# STM32WL_LHCbit.net
KiCad netlist of a schematic drawn in Altium Designer
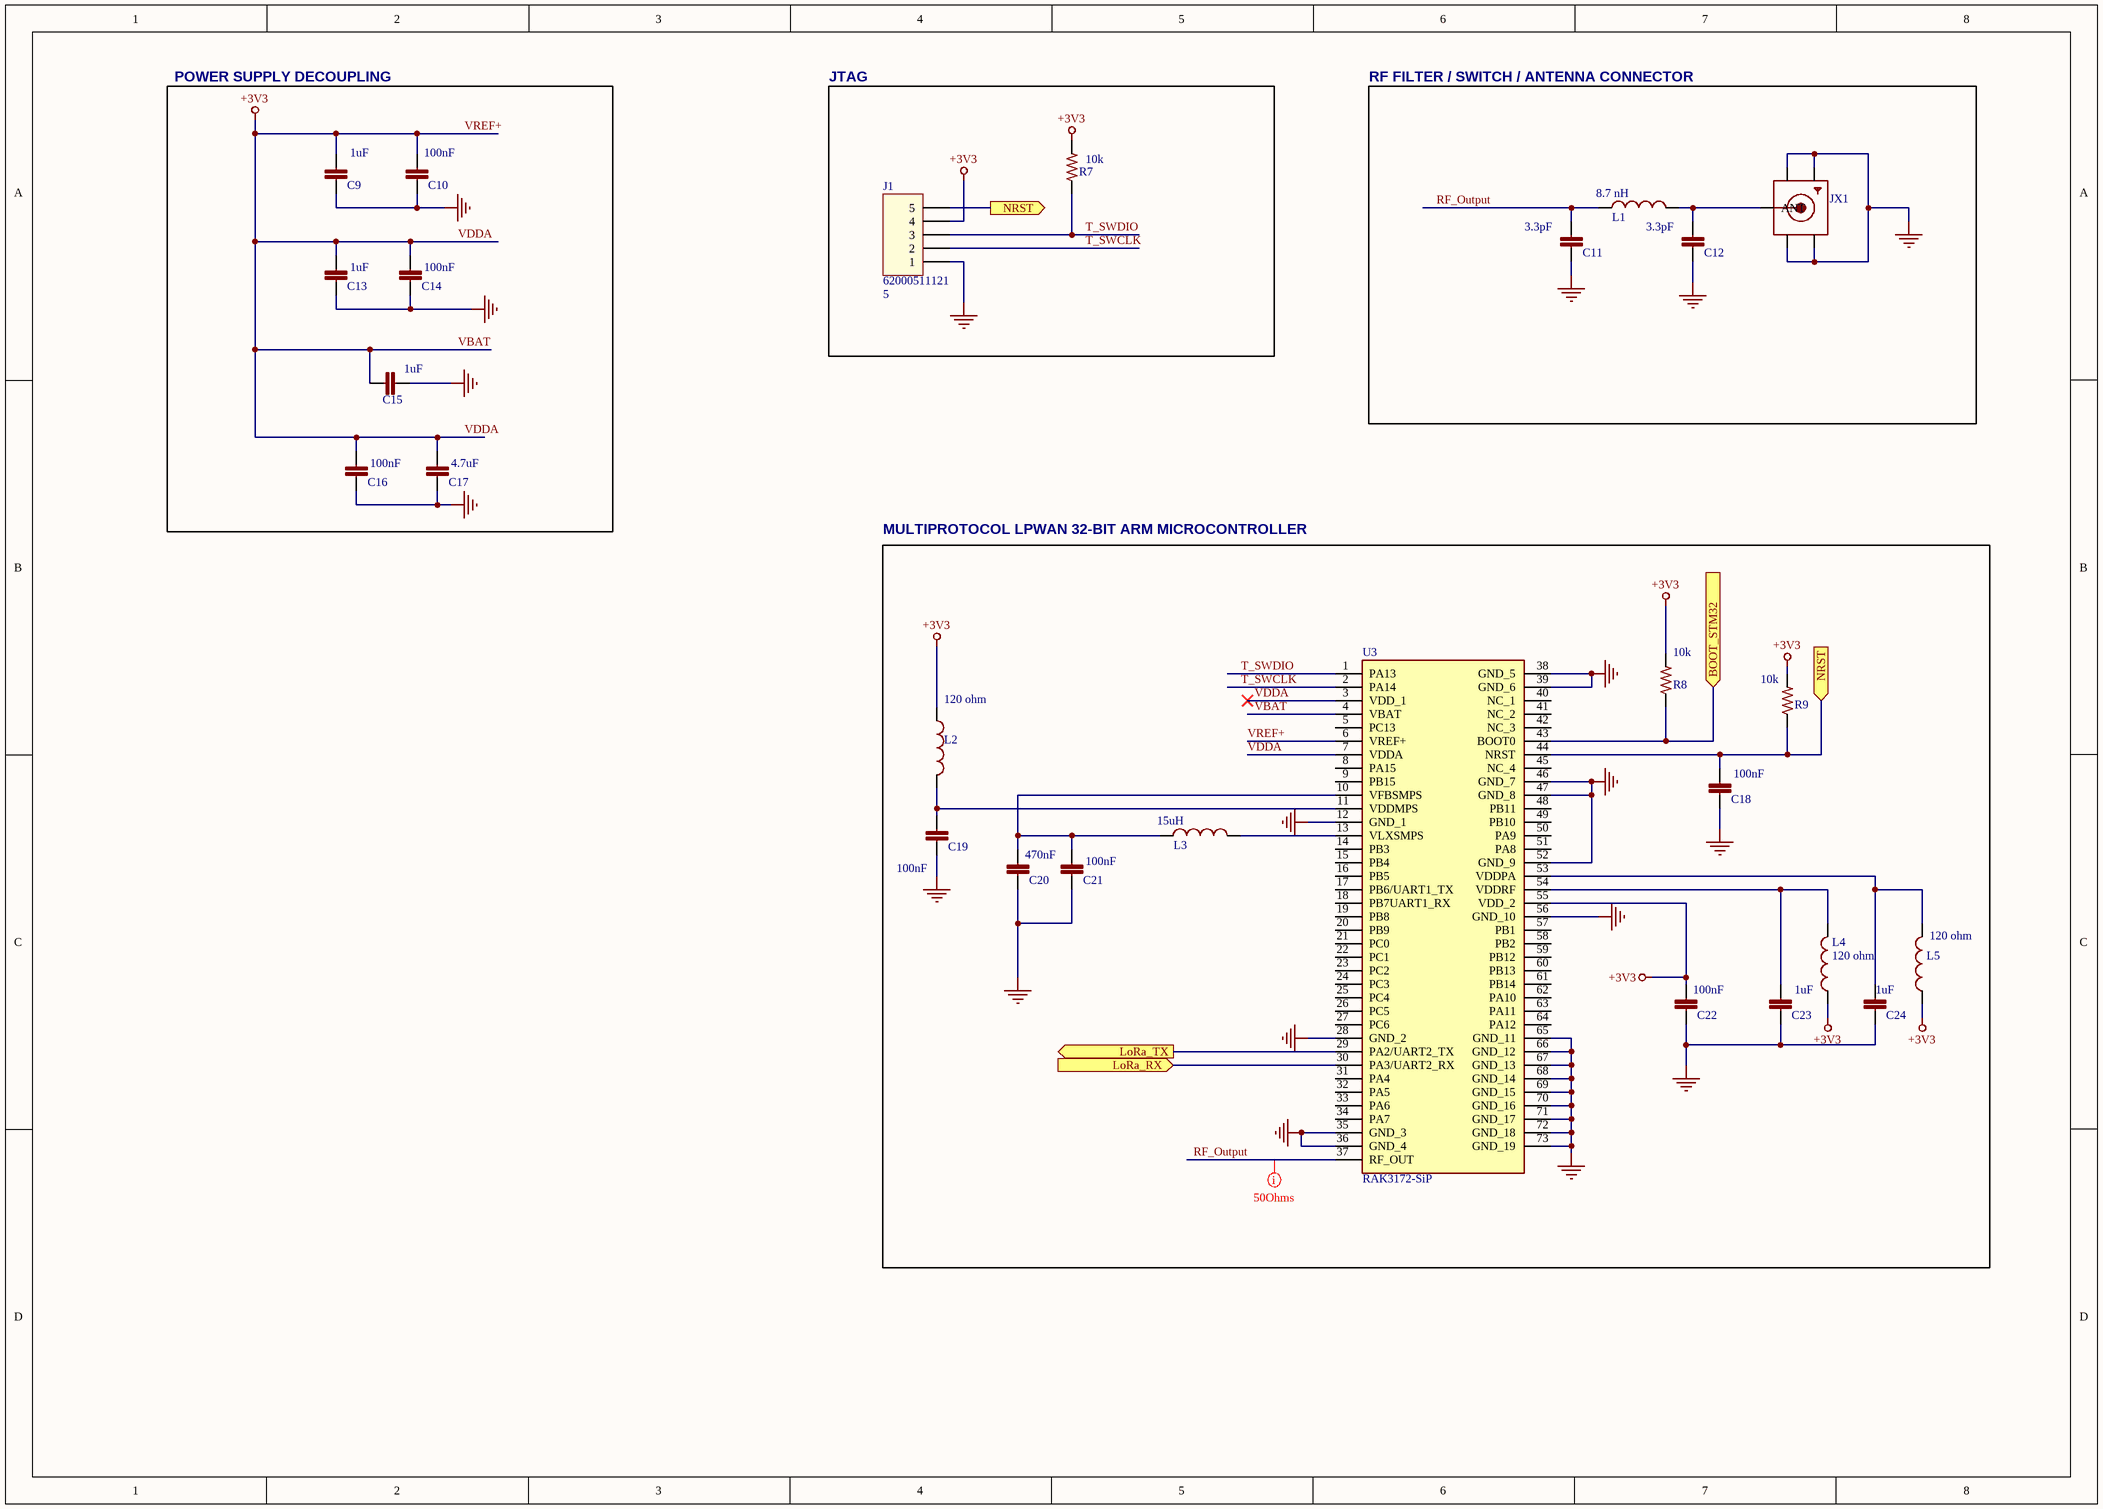
[diagram p0: STM32WL_LHCbit.SchDoc]

(export (version "E")
  (design (tool "Eeschema 10.0.6"))
  (components
    (comp (ref "C9")
      (value "1uF")
      (footprint "C0402")
      (fields (field (name "PART NUMBER") "CL05A105KA5NQNC") (field (name "Comment") "C-EUC0402"))
      (libsource (lib "rcl") (part "C-EUC0402"))
    )
    (comp (ref "C10")
      (value "100nF")
      (footprint "C0402")
      (fields (field (name "PART NUMBER") "C0402C104K8") (field (name "Comment") "C-EUC0402"))
      (libsource (lib "rcl") (part "C-EUC0402"))
    )
    (comp (ref "C11")
      (value "3.3pF")
      (footprint "C0402")
      (fields (field (name "PART NUMBER") "GRM1555C1H3R3WA01D") (field (name "Comment") "C-EUC0402"))
      (libsource (lib "") (part "C-EUC0402_1"))
    )
    (comp (ref "C12")
      (value "3.3pF")
      (footprint "C0402")
      (fields (field (name "PART NUMBER") "GRM1555C1H3R3WA01D") (field (name "Comment") "C-EUC0402"))
      (libsource (lib "") (part "C-EUC0402_1"))
    )
    (comp (ref "C13")
      (value "1uF")
      (footprint "C0402")
      (fields (field (name "PART NUMBER") "CL05A105KA5NQNC") (field (name "Comment") "C-EUC0402"))
      (libsource (lib "rcl") (part "C-EUC0402"))
    )
    (comp (ref "C14")
      (value "100nF")
      (footprint "C0402")
      (fields (field (name "PART NUMBER") "C0402C104K8") (field (name "Comment") "C-EUC0402"))
      (libsource (lib "rcl") (part "C-EUC0402"))
    )
    (comp (ref "C15")
      (value "1uF")
      (footprint "C0402")
      (fields (field (name "PART NUMBER") "CL05A105KA5NQNC") (field (name "Comment") "C-EUC0402"))
      (libsource (lib "") (part "C-EUC0402_2"))
    )
    (comp (ref "C16")
      (value "100nF")
      (footprint "C0402")
      (fields (field (name "PART NUMBER") "C0402C104K8") (field (name "Comment") "C-EUC0402"))
      (libsource (lib "rcl") (part "C-EUC0402"))
    )
    (comp (ref "C17")
      (value "4.7uF")
      (footprint "C0402")
      (fields (field (name "PART NUMBER") "CL05A475MQ5NRNC") (field (name "Comment") "C-EUC0402"))
      (libsource (lib "rcl") (part "C-EUC0402"))
    )
    (comp (ref "C18")
      (value "100nF")
      (footprint "C0402")
      (fields (field (name "PART NUMBER") "C0402C104K8") (field (name "Comment") "C-EUC0402"))
      (libsource (lib "rcl") (part "C-EUC0402"))
    )
    (comp (ref "C19")
      (value "100nF")
      (footprint "C0402")
      (fields (field (name "PART NUMBER") "C0402C104K8") (field (name "Comment") "C-EUC0402"))
      (libsource (lib "rcl") (part "C-EUC0402"))
    )
    (comp (ref "C20")
      (value "470nF")
      (footprint "C0402")
      (fields (field (name "PART NUMBER") "GRM155R61H474KE11D") (field (name "Comment") "C-EUC0402"))
      (libsource (lib "rcl") (part "C-EUC0402"))
    )
    (comp (ref "C21")
      (value "100nF")
      (footprint "C0402")
      (fields (field (name "PART NUMBER") "C0402C104K8") (field (name "Comment") "C-EUC0402"))
      (libsource (lib "rcl") (part "C-EUC0402"))
    )
    (comp (ref "C22")
      (value "100nF")
      (footprint "C0402")
      (fields (field (name "PART NUMBER") "C0402C104K8") (field (name "Comment") "C-EUC0402"))
      (libsource (lib "rcl") (part "C-EUC0402"))
    )
    (comp (ref "C23")
      (value "1uF")
      (footprint "C0402")
      (fields (field (name "PART NUMBER") "CL05A105KA5NQNC") (field (name "Comment") "C-EUC0402"))
      (libsource (lib "rcl") (part "C-EUC0402"))
    )
    (comp (ref "C24")
      (value "1uF")
      (footprint "C0402")
      (fields (field (name "PART NUMBER") "CL05A105KA5NQNC") (field (name "Comment") "C-EUC0402"))
      (libsource (lib "rcl") (part "C-EUC0402"))
    )
    (comp (ref "J1")
      (value "62000511121")
      (footprint "62000511121")
      (description "WR-PHD 2.00 mm THT Pin Header, 6p")
      (fields (field (name "ALTIUM_VALUE") "5"))
      (libsource (lib "Male_header_200mm") (part "62000511121"))
    )
    (comp (ref "JX1")
      (value "SMACONNECTOR_EDGE_UFL")
      (footprint "SMA_EDGELAUNCH_UFL")
      (fields (field (name "PART NUMBER") "SMA-J-P-H-ST-EM1"))
      (libsource (lib "TE") (part "SMACONNECTOR_EDGE_UFL"))
    )
    (comp (ref "L1")
      (value "8.7 nH")
      (footprint "L0402 - rounded")
      (fields (field (name "PART NUMBER") "LQW15AN8N7G00D") (field (name "Comment") "Ferrite bead 0402"))
      (libsource (lib "rcl") (part "L-US0402"))
    )
    (comp (ref "L2")
      (value "120 ohm")
      (footprint "L0603")
      (fields (field (name "PART NUMBER") "YI160808U121-2R5T") (field (name "Comment") "Ferrite bead 0603"))
      (libsource (lib "rcl") (part "L-US0603"))
    )
    (comp (ref "L3")
      (value "15uH")
      (footprint "L0805")
      (fields (field (name "PART NUMBER") "MLZ2012M150WTD25"))
      (libsource (lib "rcl") (part "L-US0805"))
    )
    (comp (ref "L4")
      (value "120 ohm")
      (footprint "L0603")
      (fields (field (name "PART NUMBER") "YI160808U121-2R5T") (field (name "Comment") "Ferrite bead 0603"))
      (libsource (lib "rcl") (part "L-US0603"))
    )
    (comp (ref "L5")
      (value "120 ohm")
      (footprint "L0603")
      (fields (field (name "PART NUMBER") "YI160808U121-2R5T") (field (name "Comment") "Ferrite bead 0603"))
      (libsource (lib "rcl") (part "L-US0603"))
    )
    (comp (ref "R7")
      (value "10k")
      (footprint "R0402")
      (fields (field (name "PART NUMBER") "RC0402FR-0710KL") (field (name "Comment") "R-US_R0402"))
      (libsource (lib "rcl") (part "R-US_R0402"))
    )
    (comp (ref "R8")
      (value "10k")
      (footprint "R0402")
      (fields (field (name "PART NUMBER") "RC0402FR-0710KL") (field (name "Comment") "R-US_R0402"))
      (libsource (lib "rcl") (part "R-US_R0402"))
    )
    (comp (ref "R9")
      (value "10k")
      (footprint "R0402")
      (fields (field (name "PART NUMBER") "RC0402FR-0710KL") (field (name "Comment") "R-US_R0402"))
      (libsource (lib "rcl") (part "R-US_R0402"))
    )
    (comp (ref "U3")
      (value "RAK3172-SiP")
      (footprint "RAK3172SiP")
      (description "Integrated Circuit")
      (fields (field (name "PART NUMBER") "RAK3172-SIP-9-SM-NI"))
      (libsource (lib "TE") (part "RAK3172-SiP"))
    )
  )
  (nets
    (net (code "1") (name "+3V3") (class "Default")
      (node (ref "C10") (pin "1") (pinfunction "1_1") (pintype "passive"))
      (node (ref "C13") (pin "1") (pinfunction "1_1") (pintype "passive"))
      (node (ref "C14") (pin "1") (pinfunction "1_1") (pintype "passive"))
      (node (ref "C15") (pin "1") (pinfunction "1_1") (pintype "passive"))
      (node (ref "C16") (pin "1") (pinfunction "1_1") (pintype "passive"))
      (node (ref "C17") (pin "1") (pinfunction "1_1") (pintype "passive"))
      (node (ref "C22") (pin "1") (pinfunction "1_1") (pintype "passive"))
      (node (ref "C9") (pin "1") (pinfunction "1_1") (pintype "passive"))
      (node (ref "J1") (pin "4") (pinfunction "4_4") (pintype "passive"))
      (node (ref "L2") (pin "1") (pinfunction "1_1") (pintype "passive"))
      (node (ref "L4") (pin "1") (pinfunction "1_1") (pintype "passive"))
      (node (ref "L5") (pin "1") (pinfunction "1_1") (pintype "passive"))
      (node (ref "R7") (pin "2") (pinfunction "2_2") (pintype "passive"))
      (node (ref "R8") (pin "2") (pinfunction "2_2") (pintype "passive"))
      (node (ref "R9") (pin "2") (pinfunction "2_2") (pintype "passive"))
      (node (ref "U3") (pin "3") (pinfunction "VDD_1_3") (pintype "passive"))
      (node (ref "U3") (pin "4") (pinfunction "VBAT_4") (pintype "passive"))
      (node (ref "U3") (pin "55") (pinfunction "VDD_2_55") (pintype "passive"))
      (node (ref "U3") (pin "6") (pinfunction "VREF+_6") (pintype "passive"))
      (node (ref "U3") (pin "7") (pinfunction "VDDA_7") (pintype "passive"))
    )
    (net (code "2") (name "/BOOT_STM32") (class "Default")
      (node (ref "R8") (pin "1") (pinfunction "1_1") (pintype "passive"))
      (node (ref "U3") (pin "43") (pinfunction "BOOT0_43") (pintype "passive"))
    )
    (net (code "3") (name "/LoRa_RX") (class "Default")
      (node (ref "U3") (pin "30") (pinfunction "PA3/UART2_RX_30") (pintype "passive"))
    )
    (net (code "4") (name "/LoRa_TX") (class "Default")
      (node (ref "U3") (pin "29") (pinfunction "PA2/UART2_TX_29") (pintype "passive"))
    )
    (net (code "5") (name "/NRST") (class "Default")
      (node (ref "C18") (pin "1") (pinfunction "1_1") (pintype "passive"))
      (node (ref "J1") (pin "5") (pinfunction "5_5") (pintype "passive"))
      (node (ref "R9") (pin "1") (pinfunction "1_1") (pintype "passive"))
      (node (ref "U3") (pin "44") (pinfunction "NRST_44") (pintype "passive"))
    )
    (net (code "6") (name "/RF_Output") (class "Default")
      (node (ref "C11") (pin "2") (pinfunction "2_2") (pintype "passive"))
      (node (ref "L1") (pin "1") (pinfunction "1_1") (pintype "passive"))
      (node (ref "U3") (pin "37") (pinfunction "RF_OUT_37") (pintype "passive"))
    )
    (net (code "7") (name "/T_SWCLK") (class "Default")
      (node (ref "J1") (pin "2") (pinfunction "2_2") (pintype "passive"))
      (node (ref "U3") (pin "2") (pinfunction "PA14_2") (pintype "passive"))
    )
    (net (code "8") (name "/T_SWDIO") (class "Default")
      (node (ref "J1") (pin "3") (pinfunction "3_3") (pintype "passive"))
      (node (ref "R7") (pin "1") (pinfunction "1_1") (pintype "passive"))
      (node (ref "U3") (pin "1") (pinfunction "PA13_1") (pintype "passive"))
    )
    (net (code "9") (name "GND") (class "Default")
      (node (ref "C10") (pin "2") (pinfunction "2_2") (pintype "passive"))
      (node (ref "C11") (pin "1") (pinfunction "1_1") (pintype "passive"))
      (node (ref "C12") (pin "1") (pinfunction "1_1") (pintype "passive"))
      (node (ref "C13") (pin "2") (pinfunction "2_2") (pintype "passive"))
      (node (ref "C14") (pin "2") (pinfunction "2_2") (pintype "passive"))
      (node (ref "C15") (pin "2") (pinfunction "2_2") (pintype "passive"))
      (node (ref "C16") (pin "2") (pinfunction "2_2") (pintype "passive"))
      (node (ref "C17") (pin "2") (pinfunction "2_2") (pintype "passive"))
      (node (ref "C18") (pin "2") (pinfunction "2_2") (pintype "passive"))
      (node (ref "C19") (pin "2") (pinfunction "2_2") (pintype "passive"))
      (node (ref "C20") (pin "2") (pinfunction "2_2") (pintype "passive"))
      (node (ref "C21") (pin "2") (pinfunction "2_2") (pintype "passive"))
      (node (ref "C22") (pin "2") (pinfunction "2_2") (pintype "passive"))
      (node (ref "C23") (pin "2") (pinfunction "2_2") (pintype "passive"))
      (node (ref "C24") (pin "2") (pinfunction "2_2") (pintype "passive"))
      (node (ref "C9") (pin "2") (pinfunction "2_2") (pintype "passive"))
      (node (ref "J1") (pin "1") (pinfunction "1_1") (pintype "passive"))
      (node (ref "JX1") (pin "GND@1") (pinfunction "GND1_GND@1") (pintype "power_in"))
      (node (ref "JX1") (pin "GND@2") (pinfunction "GND2_GND@2") (pintype "power_in"))
      (node (ref "JX1") (pin "GND@3") (pinfunction "GND3_GND@3") (pintype "power_in"))
      (node (ref "JX1") (pin "GND@4") (pinfunction "GND4_GND@4") (pintype "power_in"))
      (node (ref "U3") (pin "12") (pinfunction "GND_1_12") (pintype "passive"))
      (node (ref "U3") (pin "28") (pinfunction "GND_2_28") (pintype "passive"))
      (node (ref "U3") (pin "35") (pinfunction "GND_3_35") (pintype "passive"))
      (node (ref "U3") (pin "36") (pinfunction "GND_4_36") (pintype "passive"))
      (node (ref "U3") (pin "38") (pinfunction "GND_5_38") (pintype "passive"))
      (node (ref "U3") (pin "39") (pinfunction "GND_6_39") (pintype "passive"))
      (node (ref "U3") (pin "46") (pinfunction "GND_7_46") (pintype "passive"))
      (node (ref "U3") (pin "47") (pinfunction "GND_8_47") (pintype "passive"))
      (node (ref "U3") (pin "52") (pinfunction "GND_9_52") (pintype "passive"))
      (node (ref "U3") (pin "56") (pinfunction "GND_10_56") (pintype "passive"))
      (node (ref "U3") (pin "65") (pinfunction "GND_11_65") (pintype "passive"))
      (node (ref "U3") (pin "66") (pinfunction "GND_12_66") (pintype "passive"))
      (node (ref "U3") (pin "67") (pinfunction "GND_13_67") (pintype "passive"))
      (node (ref "U3") (pin "68") (pinfunction "GND_14_68") (pintype "passive"))
      (node (ref "U3") (pin "69") (pinfunction "GND_15_69") (pintype "passive"))
      (node (ref "U3") (pin "70") (pinfunction "GND_16_70") (pintype "passive"))
      (node (ref "U3") (pin "71") (pinfunction "GND_17_71") (pintype "passive"))
      (node (ref "U3") (pin "72") (pinfunction "GND_18_72") (pintype "passive"))
      (node (ref "U3") (pin "73") (pinfunction "GND_19_73") (pintype "passive"))
    )
    (net (code "10") (name "Net-(JX1-ANT)") (class "Default")
      (node (ref "C12") (pin "2") (pinfunction "2_2") (pintype "passive"))
      (node (ref "JX1") (pin "P") (pinfunction "ANT_P") (pintype "passive"))
      (node (ref "L1") (pin "2") (pinfunction "2_2") (pintype "passive"))
    )
    (net (code "11") (name "Net-(U3-VDDMPS)") (class "Default")
      (node (ref "C19") (pin "1") (pinfunction "1_1") (pintype "passive"))
      (node (ref "L2") (pin "2") (pinfunction "2_2") (pintype "passive"))
      (node (ref "U3") (pin "11") (pinfunction "VDDMPS_11") (pintype "passive"))
    )
    (net (code "12") (name "Net-(U3-VDDPA)") (class "Default")
      (node (ref "C24") (pin "1") (pinfunction "1_1") (pintype "passive"))
      (node (ref "L5") (pin "2") (pinfunction "2_2") (pintype "passive"))
      (node (ref "U3") (pin "53") (pinfunction "VDDPA_53") (pintype "passive"))
    )
    (net (code "13") (name "Net-(U3-VDDRF)") (class "Default")
      (node (ref "C23") (pin "1") (pinfunction "1_1") (pintype "passive"))
      (node (ref "L4") (pin "2") (pinfunction "2_2") (pintype "passive"))
      (node (ref "U3") (pin "54") (pinfunction "VDDRF_54") (pintype "passive"))
    )
    (net (code "14") (name "Net-(U3-VFBSMPS)") (class "Default")
      (node (ref "C20") (pin "1") (pinfunction "1_1") (pintype "passive"))
      (node (ref "C21") (pin "1") (pinfunction "1_1") (pintype "passive"))
      (node (ref "L3") (pin "1") (pinfunction "1_1") (pintype "passive"))
      (node (ref "U3") (pin "10") (pinfunction "VFBSMPS_10") (pintype "passive"))
    )
    (net (code "15") (name "Net-(U3-VLXSMPS)") (class "Default")
      (node (ref "L3") (pin "2") (pinfunction "2_2") (pintype "passive"))
      (node (ref "U3") (pin "13") (pinfunction "VLXSMPS_13") (pintype "passive"))
    )
    (net (code "16") (name "unconnected-(U3-NC_1-Pad40)") (class "Default")
      (node (ref "U3") (pin "40") (pinfunction "NC_1_40") (pintype "passive"))
    )
    (net (code "17") (name "unconnected-(U3-NC_2-Pad41)") (class "Default")
      (node (ref "U3") (pin "41") (pinfunction "NC_2_41") (pintype "passive"))
    )
    (net (code "18") (name "unconnected-(U3-NC_3-Pad42)") (class "Default")
      (node (ref "U3") (pin "42") (pinfunction "NC_3_42") (pintype "passive"))
    )
    (net (code "19") (name "unconnected-(U3-NC_4-Pad45)") (class "Default")
      (node (ref "U3") (pin "45") (pinfunction "NC_4_45") (pintype "passive"))
    )
    (net (code "20") (name "unconnected-(U3-PA4-Pad31)") (class "Default")
      (node (ref "U3") (pin "31") (pinfunction "PA4_31") (pintype "passive"))
    )
    (net (code "21") (name "unconnected-(U3-PA5-Pad32)") (class "Default")
      (node (ref "U3") (pin "32") (pinfunction "PA5_32") (pintype "passive"))
    )
    (net (code "22") (name "unconnected-(U3-PA6-Pad33)") (class "Default")
      (node (ref "U3") (pin "33") (pinfunction "PA6_33") (pintype "passive"))
    )
    (net (code "23") (name "unconnected-(U3-PA7-Pad34)") (class "Default")
      (node (ref "U3") (pin "34") (pinfunction "PA7_34") (pintype "passive"))
    )
    (net (code "24") (name "unconnected-(U3-PA8-Pad51)") (class "Default")
      (node (ref "U3") (pin "51") (pinfunction "PA8_51") (pintype "passive"))
    )
    (net (code "25") (name "unconnected-(U3-PA9-Pad50)") (class "Default")
      (node (ref "U3") (pin "50") (pinfunction "PA9_50") (pintype "passive"))
    )
    (net (code "26") (name "unconnected-(U3-PA10-Pad62)") (class "Default")
      (node (ref "U3") (pin "62") (pinfunction "PA10_62") (pintype "passive"))
    )
    (net (code "27") (name "unconnected-(U3-PA11-Pad63)") (class "Default")
      (node (ref "U3") (pin "63") (pinfunction "PA11_63") (pintype "passive"))
    )
    (net (code "28") (name "unconnected-(U3-PA12-Pad64)") (class "Default")
      (node (ref "U3") (pin "64") (pinfunction "PA12_64") (pintype "passive"))
    )
    (net (code "29") (name "unconnected-(U3-PA15-Pad8)") (class "Default")
      (node (ref "U3") (pin "8") (pinfunction "PA15_8") (pintype "passive"))
    )
    (net (code "30") (name "unconnected-(U3-PB1-Pad57)") (class "Default")
      (node (ref "U3") (pin "57") (pinfunction "PB1_57") (pintype "passive"))
    )
    (net (code "31") (name "unconnected-(U3-PB2-Pad58)") (class "Default")
      (node (ref "U3") (pin "58") (pinfunction "PB2_58") (pintype "passive"))
    )
    (net (code "32") (name "unconnected-(U3-PB3-Pad14)") (class "Default")
      (node (ref "U3") (pin "14") (pinfunction "PB3_14") (pintype "passive"))
    )
    (net (code "33") (name "unconnected-(U3-PB4-Pad15)") (class "Default")
      (node (ref "U3") (pin "15") (pinfunction "PB4_15") (pintype "passive"))
    )
    (net (code "34") (name "unconnected-(U3-PB5-Pad16)") (class "Default")
      (node (ref "U3") (pin "16") (pinfunction "PB5_16") (pintype "passive"))
    )
    (net (code "35") (name "unconnected-(U3-PB6{slash}UART1_TX-Pad17)") (class "Default")
      (node (ref "U3") (pin "17") (pinfunction "PB6/UART1_TX_17") (pintype "passive"))
    )
    (net (code "36") (name "unconnected-(U3-PB7UART1_RX-Pad18)") (class "Default")
      (node (ref "U3") (pin "18") (pinfunction "PB7UART1_RX_18") (pintype "passive"))
    )
    (net (code "37") (name "unconnected-(U3-PB8-Pad19)") (class "Default")
      (node (ref "U3") (pin "19") (pinfunction "PB8_19") (pintype "passive"))
    )
    (net (code "38") (name "unconnected-(U3-PB9-Pad20)") (class "Default")
      (node (ref "U3") (pin "20") (pinfunction "PB9_20") (pintype "passive"))
    )
    (net (code "39") (name "unconnected-(U3-PB10-Pad49)") (class "Default")
      (node (ref "U3") (pin "49") (pinfunction "PB10_49") (pintype "passive"))
    )
    (net (code "40") (name "unconnected-(U3-PB11-Pad48)") (class "Default")
      (node (ref "U3") (pin "48") (pinfunction "PB11_48") (pintype "passive"))
    )
    (net (code "41") (name "unconnected-(U3-PB12-Pad59)") (class "Default")
      (node (ref "U3") (pin "59") (pinfunction "PB12_59") (pintype "passive"))
    )
    (net (code "42") (name "unconnected-(U3-PB13-Pad60)") (class "Default")
      (node (ref "U3") (pin "60") (pinfunction "PB13_60") (pintype "passive"))
    )
    (net (code "43") (name "unconnected-(U3-PB14-Pad61)") (class "Default")
      (node (ref "U3") (pin "61") (pinfunction "PB14_61") (pintype "passive"))
    )
    (net (code "44") (name "unconnected-(U3-PB15-Pad9)") (class "Default")
      (node (ref "U3") (pin "9") (pinfunction "PB15_9") (pintype "passive"))
    )
    (net (code "45") (name "unconnected-(U3-PC0-Pad21)") (class "Default")
      (node (ref "U3") (pin "21") (pinfunction "PC0_21") (pintype "passive"))
    )
    (net (code "46") (name "unconnected-(U3-PC1-Pad22)") (class "Default")
      (node (ref "U3") (pin "22") (pinfunction "PC1_22") (pintype "passive"))
    )
    (net (code "47") (name "unconnected-(U3-PC2-Pad23)") (class "Default")
      (node (ref "U3") (pin "23") (pinfunction "PC2_23") (pintype "passive"))
    )
    (net (code "48") (name "unconnected-(U3-PC3-Pad24)") (class "Default")
      (node (ref "U3") (pin "24") (pinfunction "PC3_24") (pintype "passive"))
    )
    (net (code "49") (name "unconnected-(U3-PC4-Pad25)") (class "Default")
      (node (ref "U3") (pin "25") (pinfunction "PC4_25") (pintype "passive"))
    )
    (net (code "50") (name "unconnected-(U3-PC5-Pad26)") (class "Default")
      (node (ref "U3") (pin "26") (pinfunction "PC5_26") (pintype "passive"))
    )
    (net (code "51") (name "unconnected-(U3-PC6-Pad27)") (class "Default")
      (node (ref "U3") (pin "27") (pinfunction "PC6_27") (pintype "passive"))
    )
    (net (code "52") (name "unconnected-(U3-PC13-Pad5)") (class "Default")
      (node (ref "U3") (pin "5") (pinfunction "PC13_5") (pintype "passive"))
    )
  )
)
